# led_driver3.net
KiCad netlist of a schematic drawn in EAGLE
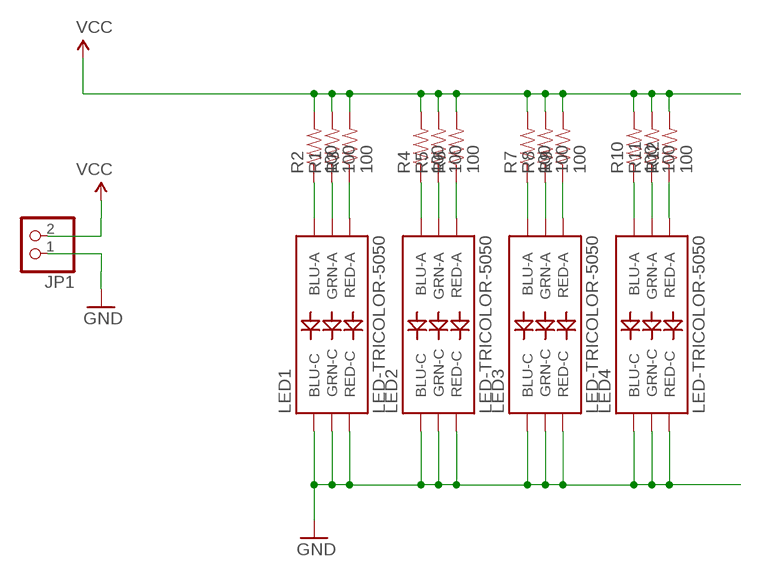
[diagram p0: schematic, sheet 1]

(export (version "E")
  (design (tool "Eeschema 10.0.6"))
  (components
    (comp (ref "JP1")
      (value "PINHD-1X2")
      (footprint "eagle-import:1X02")
      (libsource (lib "eagle-import") (part "PINHD-1X2"))
    )
    (comp (ref "LED1")
      (value "LED-TRICOLOR-5050")
      (footprint "eagle-import:LED-TRICOLOR-5050")
      (libsource (lib "eagle-import") (part "LED-TRICOLOR-5050"))
    )
    (comp (ref "LED2")
      (value "LED-TRICOLOR-5050")
      (footprint "eagle-import:LED-TRICOLOR-5050")
      (libsource (lib "eagle-import") (part "LED-TRICOLOR-5050"))
    )
    (comp (ref "LED3")
      (value "LED-TRICOLOR-5050")
      (footprint "eagle-import:LED-TRICOLOR-5050")
      (libsource (lib "eagle-import") (part "LED-TRICOLOR-5050"))
    )
    (comp (ref "LED4")
      (value "LED-TRICOLOR-5050")
      (footprint "eagle-import:LED-TRICOLOR-5050")
      (libsource (lib "eagle-import") (part "LED-TRICOLOR-5050"))
    )
    (comp (ref "R1")
      (value "100")
      (footprint "eagle-import:0603-RES")
      (libsource (lib "eagle-import") (part "RESISTOR0603-RES"))
    )
    (comp (ref "R2")
      (value "100")
      (footprint "eagle-import:0603-RES")
      (libsource (lib "eagle-import") (part "RESISTOR0603-RES"))
    )
    (comp (ref "R3")
      (value "100")
      (footprint "eagle-import:0603-RES")
      (libsource (lib "eagle-import") (part "RESISTOR0603-RES"))
    )
    (comp (ref "R4")
      (value "100")
      (footprint "eagle-import:0603-RES")
      (libsource (lib "eagle-import") (part "RESISTOR0603-RES"))
    )
    (comp (ref "R5")
      (value "100")
      (footprint "eagle-import:0603-RES")
      (libsource (lib "eagle-import") (part "RESISTOR0603-RES"))
    )
    (comp (ref "R6")
      (value "100")
      (footprint "eagle-import:0603-RES")
      (libsource (lib "eagle-import") (part "RESISTOR0603-RES"))
    )
    (comp (ref "R7")
      (value "100")
      (footprint "eagle-import:0603-RES")
      (libsource (lib "eagle-import") (part "RESISTOR0603-RES"))
    )
    (comp (ref "R8")
      (value "100")
      (footprint "eagle-import:0603-RES")
      (libsource (lib "eagle-import") (part "RESISTOR0603-RES"))
    )
    (comp (ref "R9")
      (value "100")
      (footprint "eagle-import:0603-RES")
      (libsource (lib "eagle-import") (part "RESISTOR0603-RES"))
    )
    (comp (ref "R10")
      (value "100")
      (footprint "eagle-import:0603-RES")
      (libsource (lib "eagle-import") (part "RESISTOR0603-RES"))
    )
    (comp (ref "R11")
      (value "100")
      (footprint "eagle-import:0603-RES")
      (libsource (lib "eagle-import") (part "RESISTOR0603-RES"))
    )
    (comp (ref "R12")
      (value "100")
      (footprint "eagle-import:0603-RES")
      (libsource (lib "eagle-import") (part "RESISTOR0603-RES"))
    )
  )
  (nets
    (net (code "1") (name "GND") (class "Default")
      (node (ref "JP1") (pin "1") (pinfunction "1_1") (pintype "passive"))
      (node (ref "LED1") (pin "4") (pinfunction "BLU-C_4") (pintype "bidirectional"))
      (node (ref "LED1") (pin "5") (pinfunction "RED-C_5") (pintype "bidirectional"))
      (node (ref "LED1") (pin "6") (pinfunction "GRN-C_6") (pintype "bidirectional"))
      (node (ref "LED2") (pin "4") (pinfunction "BLU-C_4") (pintype "bidirectional"))
      (node (ref "LED2") (pin "5") (pinfunction "RED-C_5") (pintype "bidirectional"))
      (node (ref "LED2") (pin "6") (pinfunction "GRN-C_6") (pintype "bidirectional"))
      (node (ref "LED3") (pin "4") (pinfunction "BLU-C_4") (pintype "bidirectional"))
      (node (ref "LED3") (pin "5") (pinfunction "RED-C_5") (pintype "bidirectional"))
      (node (ref "LED3") (pin "6") (pinfunction "GRN-C_6") (pintype "bidirectional"))
      (node (ref "LED4") (pin "4") (pinfunction "BLU-C_4") (pintype "bidirectional"))
      (node (ref "LED4") (pin "5") (pinfunction "RED-C_5") (pintype "bidirectional"))
      (node (ref "LED4") (pin "6") (pinfunction "GRN-C_6") (pintype "bidirectional"))
    )
    (net (code "2") (name "Net-(LED1-BLU-A)") (class "Default")
      (node (ref "LED1") (pin "3") (pinfunction "BLU-A_3") (pintype "bidirectional"))
      (node (ref "R2") (pin "1") (pinfunction "1_1") (pintype "passive"))
    )
    (net (code "3") (name "Net-(LED1-GRN-A)") (class "Default")
      (node (ref "LED1") (pin "1") (pinfunction "GRN-A_1") (pintype "bidirectional"))
      (node (ref "R1") (pin "1") (pinfunction "1_1") (pintype "passive"))
    )
    (net (code "4") (name "Net-(LED1-RED-A)") (class "Default")
      (node (ref "LED1") (pin "2") (pinfunction "RED-A_2") (pintype "bidirectional"))
      (node (ref "R3") (pin "1") (pinfunction "1_1") (pintype "passive"))
    )
    (net (code "5") (name "Net-(LED2-BLU-A)") (class "Default")
      (node (ref "LED2") (pin "3") (pinfunction "BLU-A_3") (pintype "bidirectional"))
      (node (ref "R4") (pin "1") (pinfunction "1_1") (pintype "passive"))
    )
    (net (code "6") (name "Net-(LED2-GRN-A)") (class "Default")
      (node (ref "LED2") (pin "1") (pinfunction "GRN-A_1") (pintype "bidirectional"))
      (node (ref "R5") (pin "1") (pinfunction "1_1") (pintype "passive"))
    )
    (net (code "7") (name "Net-(LED2-RED-A)") (class "Default")
      (node (ref "LED2") (pin "2") (pinfunction "RED-A_2") (pintype "bidirectional"))
      (node (ref "R6") (pin "1") (pinfunction "1_1") (pintype "passive"))
    )
    (net (code "8") (name "Net-(LED3-BLU-A)") (class "Default")
      (node (ref "LED3") (pin "3") (pinfunction "BLU-A_3") (pintype "bidirectional"))
      (node (ref "R7") (pin "1") (pinfunction "1_1") (pintype "passive"))
    )
    (net (code "9") (name "Net-(LED3-GRN-A)") (class "Default")
      (node (ref "LED3") (pin "1") (pinfunction "GRN-A_1") (pintype "bidirectional"))
      (node (ref "R8") (pin "1") (pinfunction "1_1") (pintype "passive"))
    )
    (net (code "10") (name "Net-(LED3-RED-A)") (class "Default")
      (node (ref "LED3") (pin "2") (pinfunction "RED-A_2") (pintype "bidirectional"))
      (node (ref "R9") (pin "1") (pinfunction "1_1") (pintype "passive"))
    )
    (net (code "11") (name "Net-(LED4-BLU-A)") (class "Default")
      (node (ref "LED4") (pin "3") (pinfunction "BLU-A_3") (pintype "bidirectional"))
      (node (ref "R10") (pin "1") (pinfunction "1_1") (pintype "passive"))
    )
    (net (code "12") (name "Net-(LED4-GRN-A)") (class "Default")
      (node (ref "LED4") (pin "1") (pinfunction "GRN-A_1") (pintype "bidirectional"))
      (node (ref "R11") (pin "1") (pinfunction "1_1") (pintype "passive"))
    )
    (net (code "13") (name "Net-(LED4-RED-A)") (class "Default")
      (node (ref "LED4") (pin "2") (pinfunction "RED-A_2") (pintype "bidirectional"))
      (node (ref "R12") (pin "1") (pinfunction "1_1") (pintype "passive"))
    )
    (net (code "14") (name "VCC") (class "Default")
      (node (ref "JP1") (pin "2") (pinfunction "2_2") (pintype "passive"))
      (node (ref "R1") (pin "2") (pinfunction "2_2") (pintype "passive"))
      (node (ref "R10") (pin "2") (pinfunction "2_2") (pintype "passive"))
      (node (ref "R11") (pin "2") (pinfunction "2_2") (pintype "passive"))
      (node (ref "R12") (pin "2") (pinfunction "2_2") (pintype "passive"))
      (node (ref "R2") (pin "2") (pinfunction "2_2") (pintype "passive"))
      (node (ref "R3") (pin "2") (pinfunction "2_2") (pintype "passive"))
      (node (ref "R4") (pin "2") (pinfunction "2_2") (pintype "passive"))
      (node (ref "R5") (pin "2") (pinfunction "2_2") (pintype "passive"))
      (node (ref "R6") (pin "2") (pinfunction "2_2") (pintype "passive"))
      (node (ref "R7") (pin "2") (pinfunction "2_2") (pintype "passive"))
      (node (ref "R8") (pin "2") (pinfunction "2_2") (pintype "passive"))
      (node (ref "R9") (pin "2") (pinfunction "2_2") (pintype "passive"))
    )
  )
)
